# kt404c.net
KiCad netlist of a schematic drawn in Altium Designer
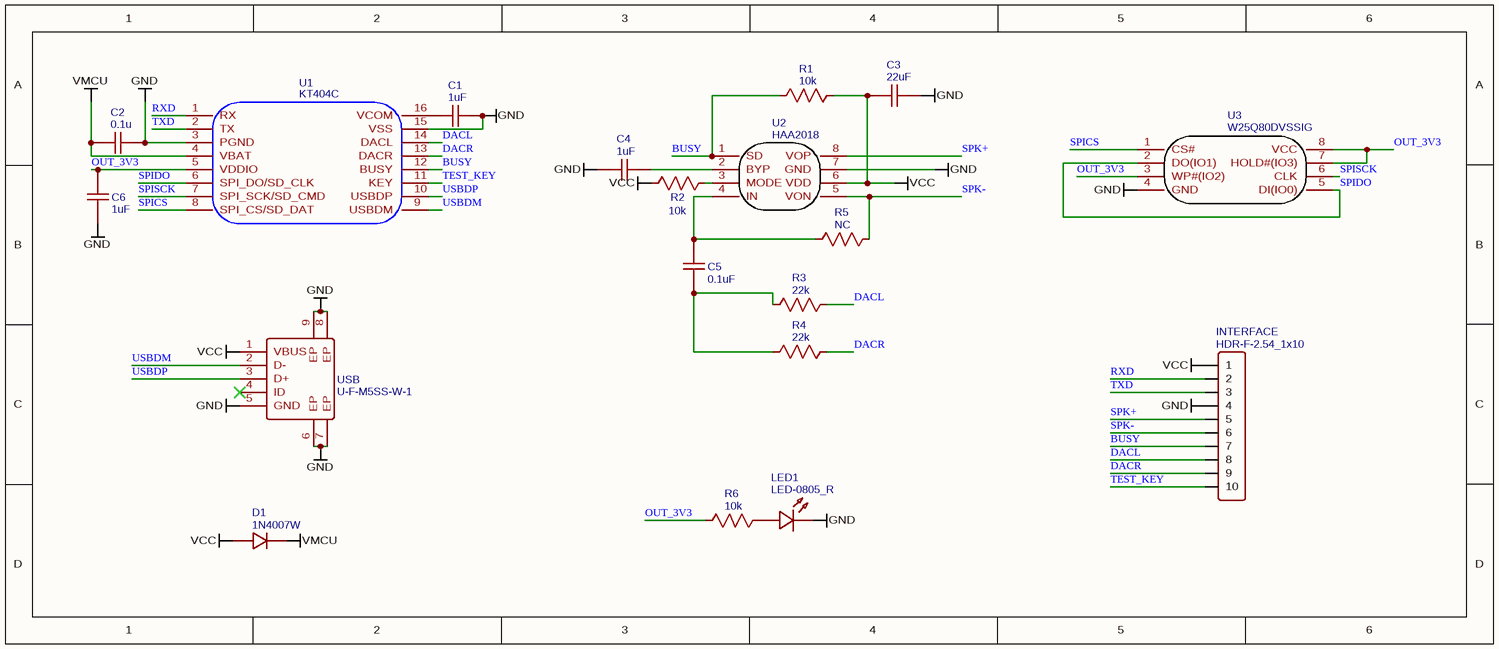
[diagram p0: kt404c.schdoc]

(export (version "E")
  (design (tool "Eeschema 10.0.6"))
  (components
    (comp (ref "C1")
      (value "1uF")
      (footprint "C0805")
      (fields (field (name "BOM_SUPPLIER PART") "C16834") (field (name "CONTRIBUTOR") "LCEDA_Lib"))
      (libsource (lib "altium-import") (part "root_0_1uF_"))
    )
    (comp (ref "C2")
      (value "0.1u")
      (footprint "C0805")
      (fields (field (name "BOM_SUPPLIER PART") "C1760") (field (name "CONTRIBUTOR") "LCEDA_Lib"))
      (libsource (lib "altium-import") (part "root_0_0.1u_"))
    )
    (comp (ref "C3")
      (value "22uF")
      (footprint "C0805")
      (fields (field (name "BOM_SUPPLIER PART") "C385040") (field (name "CONTRIBUTOR") "LCEDA_Lib"))
      (libsource (lib "altium-import") (part "root_0_22uF_"))
    )
    (comp (ref "C4")
      (value "1uF")
      (footprint "C0805")
      (fields (field (name "BOM_SUPPLIER PART") "C16834") (field (name "CONTRIBUTOR") "LCEDA_Lib"))
      (libsource (lib "altium-import") (part "root_0_1uF_"))
    )
    (comp (ref "C5")
      (value "0.1uF")
      (footprint "C0805")
      (fields (field (name "BOM_SUPPLIER PART") "C1760") (field (name "CONTRIBUTOR") "LCEDA_Lib"))
      (libsource (lib "altium-import") (part "root_3_0.1uF_"))
    )
    (comp (ref "C6")
      (value "1uF")
      (footprint "C0805")
      (fields (field (name "BOM_SUPPLIER PART") "C16834") (field (name "CONTRIBUTOR") "LCEDA_Lib"))
      (libsource (lib "altium-import") (part "root_3_1uF_"))
    )
    (comp (ref "D1")
      (value "1N4007W")
      (footprint "SOD-123_L2.8-W1.8-LS3.7-RD")
      (fields (field (name "BOM_SUPPLIER PART") "C328592") (field (name "CONTRIBUTOR") "LCEDA_Lib"))
      (libsource (lib "altium-import") (part "root_0_1N4007W_"))
    )
    (comp (ref "INTERFACE")
      (value "HDR-F-2.54_1x10")
      (footprint "HDR-F-2.54_1X10")
      (fields (field (name "BOM_SUPPLIER PART") "C57369") (field (name "CONTRIBUTOR") "LCEDA_Lib"))
      (libsource (lib "altium-import") (part "root_0_HDR-F-2.54_1x10_"))
    )
    (comp (ref "LED1")
      (value "LED-0805_R")
      (footprint "LED0805_RED")
      (fields
        (field (name "BOM_MANUFACTURER PART") "17-21SURC/S530-A3/TR8")
        (field (name "BOM_SUPPLIER PART") "C72037")
        (field (name "CONTRIBUTOR") "LCEDA_Lib")
      )
      (libsource (lib "altium-import") (part "root_0_LED-0805_R_"))
    )
    (comp (ref "R1")
      (value "10k")
      (footprint "R0805")
      (fields (field (name "BOM_SUPPLIER PART") "C2759650") (field (name "CONTRIBUTOR") "LCEDA_Lib"))
      (libsource (lib "altium-import") (part "root_0_10k_"))
    )
    (comp (ref "R2")
      (value "10k")
      (footprint "R0805")
      (fields (field (name "BOM_SUPPLIER PART") "C2759650") (field (name "CONTRIBUTOR") "LCEDA_Lib"))
      (libsource (lib "altium-import") (part "root_0_10k_"))
    )
    (comp (ref "R3")
      (value "22k")
      (footprint "R0805")
      (fields (field (name "BOM_SUPPLIER PART") "C114565") (field (name "CONTRIBUTOR") "LCEDA_Lib"))
      (libsource (lib "altium-import") (part "root_0_22k_"))
    )
    (comp (ref "R4")
      (value "22k")
      (footprint "R0805")
      (fields (field (name "BOM_SUPPLIER PART") "C114565") (field (name "CONTRIBUTOR") "LCEDA_Lib"))
      (libsource (lib "altium-import") (part "root_0_22k_"))
    )
    (comp (ref "R5")
      (value "NC")
      (footprint "R0805")
      (fields (field (name "CONTRIBUTOR") "LCEDA_Lib"))
      (libsource (lib "altium-import") (part "root_0_NC_"))
    )
    (comp (ref "R6")
      (value "10k")
      (footprint "R0805")
      (fields (field (name "BOM_SUPPLIER PART") "C2759650") (field (name "CONTRIBUTOR") "LCEDA_Lib"))
      (libsource (lib "altium-import") (part "root_0_10k_"))
    )
    (comp (ref "U1")
      (value "KT404C")
      (footprint "SOP16")
      (fields (field (name "CONTRIBUTOR") "BardYuan"))
      (libsource (lib "altium-import") (part "root_0_KT404C_"))
    )
    (comp (ref "U2")
      (value "HAA2018")
      (footprint "SOP8")
      (fields (field (name "CONTRIBUTOR") "xf1619"))
      (libsource (lib "altium-import") (part "root_0_HAA2018_"))
    )
    (comp (ref "U3")
      (value "W25Q80DVSSIG")
      (footprint "SOIC-8_L5.3-W5.3-P1.27-LS8.0-BL")
      (fields (field (name "BOM_SUPPLIER PART") "C14086"))
      (libsource (lib "altium-import") (part "root_0_W25Q80DVSSIG_"))
    )
    (comp (ref "USB")
      (value "U-F-M5SS-W-1")
      (footprint "MICRO-USB-SMD_MICRO-USB-A11")
      (fields (field (name "BOM_SUPPLIER PART") "C145783") (field (name "CONTRIBUTOR") "LCSC"))
      (libsource (lib "altium-import") (part "root_0_U-F-M5SS-W-1_"))
    )
  )
  (nets
    (net (code "1") (name "/BUSY") (class "Default")
      (node (ref "INTERFACE") (pin "7") (pinfunction "7_7") (pintype "passive"))
      (node (ref "R1") (pin "1") (pinfunction "1_1") (pintype "passive"))
      (node (ref "U1") (pin "12") (pinfunction "BUSY_12") (pintype "passive"))
      (node (ref "U2") (pin "1") (pinfunction "SD_1") (pintype "passive"))
    )
    (net (code "2") (name "/DACL") (class "Default")
      (node (ref "INTERFACE") (pin "8") (pinfunction "8_8") (pintype "passive"))
      (node (ref "R3") (pin "2") (pinfunction "2_2") (pintype "passive"))
      (node (ref "U1") (pin "14") (pinfunction "DACL_14") (pintype "passive"))
    )
    (net (code "3") (name "/DACR") (class "Default")
      (node (ref "INTERFACE") (pin "9") (pinfunction "9_9") (pintype "passive"))
      (node (ref "R4") (pin "2") (pinfunction "2_2") (pintype "passive"))
      (node (ref "U1") (pin "13") (pinfunction "DACR_13") (pintype "passive"))
    )
    (net (code "4") (name "/OUT_3V3") (class "Default")
      (node (ref "C6") (pin "1") (pinfunction "1_1") (pintype "passive"))
      (node (ref "R6") (pin "1") (pinfunction "1_1") (pintype "passive"))
      (node (ref "U1") (pin "5") (pinfunction "VDDIO_5") (pintype "passive"))
      (node (ref "U3") (pin "3") (pinfunction "WP#(IO2)_3") (pintype "passive"))
      (node (ref "U3") (pin "7") (pinfunction "HOLD#(IO3)_7") (pintype "passive"))
      (node (ref "U3") (pin "8") (pinfunction "VCC_8") (pintype "passive"))
    )
    (net (code "5") (name "/RXD") (class "Default")
      (node (ref "INTERFACE") (pin "2") (pinfunction "2_2") (pintype "passive"))
      (node (ref "U1") (pin "1") (pinfunction "RX_1") (pintype "passive"))
    )
    (net (code "6") (name "/SPICS") (class "Default")
      (node (ref "U1") (pin "8") (pinfunction "SPI_CS/SD_DAT_8") (pintype "passive"))
      (node (ref "U3") (pin "1") (pinfunction "CS#_1") (pintype "passive"))
    )
    (net (code "7") (name "/SPIDO") (class "Default")
      (node (ref "U1") (pin "6") (pinfunction "SPI_DO/SD_CLK_6") (pintype "passive"))
      (node (ref "U3") (pin "2") (pinfunction "DO(IO1)_2") (pintype "passive"))
      (node (ref "U3") (pin "5") (pinfunction "DI(IO0)_5") (pintype "passive"))
    )
    (net (code "8") (name "/SPISCK") (class "Default")
      (node (ref "U1") (pin "7") (pinfunction "SPI_SCK/SD_CMD_7") (pintype "passive"))
      (node (ref "U3") (pin "6") (pinfunction "CLK_6") (pintype "passive"))
    )
    (net (code "9") (name "/SPK+") (class "Default")
      (node (ref "INTERFACE") (pin "5") (pinfunction "5_5") (pintype "passive"))
      (node (ref "U2") (pin "8") (pinfunction "VOP_8") (pintype "passive"))
    )
    (net (code "10") (name "/SPK-") (class "Default")
      (node (ref "INTERFACE") (pin "6") (pinfunction "6_6") (pintype "passive"))
      (node (ref "R5") (pin "2") (pinfunction "2_2") (pintype "passive"))
      (node (ref "U2") (pin "5") (pinfunction "VON_5") (pintype "passive"))
    )
    (net (code "11") (name "/TEST_KEY") (class "Default")
      (node (ref "INTERFACE") (pin "10") (pinfunction "10_10") (pintype "passive"))
      (node (ref "U1") (pin "11") (pinfunction "KEY_11") (pintype "passive"))
    )
    (net (code "12") (name "/TXD") (class "Default")
      (node (ref "INTERFACE") (pin "3") (pinfunction "3_3") (pintype "passive"))
      (node (ref "U1") (pin "2") (pinfunction "TX_2") (pintype "passive"))
    )
    (net (code "13") (name "/USBDM") (class "Default")
      (node (ref "U1") (pin "9") (pinfunction "USBDM_9") (pintype "passive"))
      (node (ref "USB") (pin "2") (pinfunction "D-_2") (pintype "passive"))
    )
    (net (code "14") (name "/USBDP") (class "Default")
      (node (ref "U1") (pin "10") (pinfunction "USBDP_10") (pintype "passive"))
      (node (ref "USB") (pin "3") (pinfunction "D+_3") (pintype "passive"))
    )
    (net (code "15") (name "GND") (class "Default")
      (node (ref "C1") (pin "2") (pinfunction "2_2") (pintype "passive"))
      (node (ref "C2") (pin "2") (pinfunction "2_2") (pintype "passive"))
      (node (ref "C3") (pin "2") (pinfunction "2_2") (pintype "passive"))
      (node (ref "C4") (pin "1") (pinfunction "1_1") (pintype "passive"))
      (node (ref "C6") (pin "2") (pinfunction "2_2") (pintype "passive"))
      (node (ref "INTERFACE") (pin "4") (pinfunction "4_4") (pintype "passive"))
      (node (ref "LED1") (pin "2") (pinfunction "2_2") (pintype "passive"))
      (node (ref "U1") (pin "15") (pinfunction "VSS_15") (pintype "passive"))
      (node (ref "U1") (pin "3") (pinfunction "PGND_3") (pintype "passive"))
      (node (ref "U2") (pin "7") (pinfunction "GND_7") (pintype "passive"))
      (node (ref "U3") (pin "4") (pinfunction "GND_4") (pintype "passive"))
      (node (ref "USB") (pin "5") (pinfunction "GND_5") (pintype "passive"))
      (node (ref "USB") (pin "6") (pinfunction "EP_6") (pintype "passive"))
      (node (ref "USB") (pin "7") (pinfunction "EP_7") (pintype "passive"))
      (node (ref "USB") (pin "8") (pinfunction "EP_8") (pintype "passive"))
      (node (ref "USB") (pin "9") (pinfunction "EP_9") (pintype "passive"))
    )
    (net (code "16") (name "Net-(C5-Pad2)") (class "Default")
      (node (ref "C5") (pin "2") (pinfunction "2_2") (pintype "passive"))
      (node (ref "R3") (pin "1") (pinfunction "1_1") (pintype "passive"))
      (node (ref "R4") (pin "1") (pinfunction "1_1") (pintype "passive"))
    )
    (net (code "17") (name "Net-(LED1-Pad1)") (class "Default")
      (node (ref "LED1") (pin "1") (pinfunction "1_1") (pintype "passive"))
      (node (ref "R6") (pin "2") (pinfunction "2_2") (pintype "passive"))
    )
    (net (code "18") (name "Net-(U1-VCOM)") (class "Default")
      (node (ref "C1") (pin "1") (pinfunction "1_1") (pintype "passive"))
      (node (ref "U1") (pin "16") (pinfunction "VCOM_16") (pintype "passive"))
    )
    (net (code "19") (name "Net-(U2-BYP)") (class "Default")
      (node (ref "C4") (pin "2") (pinfunction "2_2") (pintype "passive"))
      (node (ref "U2") (pin "2") (pinfunction "BYP_2") (pintype "passive"))
    )
    (net (code "20") (name "Net-(U2-IN)") (class "Default")
      (node (ref "C5") (pin "1") (pinfunction "1_1") (pintype "passive"))
      (node (ref "R5") (pin "1") (pinfunction "1_1") (pintype "passive"))
      (node (ref "U2") (pin "4") (pinfunction "IN_4") (pintype "passive"))
    )
    (net (code "21") (name "Net-(U2-MODE)") (class "Default")
      (node (ref "R2") (pin "2") (pinfunction "2_2") (pintype "passive"))
      (node (ref "U2") (pin "3") (pinfunction "MODE_3") (pintype "passive"))
    )
    (net (code "22") (name "VCC") (class "Default")
      (node (ref "C3") (pin "1") (pinfunction "1_1") (pintype "passive"))
      (node (ref "D1") (pin "2") (pinfunction "2_2") (pintype "passive"))
      (node (ref "INTERFACE") (pin "1") (pinfunction "1_1") (pintype "passive"))
      (node (ref "R1") (pin "2") (pinfunction "2_2") (pintype "passive"))
      (node (ref "R2") (pin "1") (pinfunction "1_1") (pintype "passive"))
      (node (ref "U2") (pin "6") (pinfunction "VDD_6") (pintype "passive"))
      (node (ref "USB") (pin "1") (pinfunction "VBUS_1") (pintype "passive"))
    )
    (net (code "23") (name "VMCU") (class "Default")
      (node (ref "C2") (pin "1") (pinfunction "1_1") (pintype "passive"))
      (node (ref "D1") (pin "1") (pinfunction "1_1") (pintype "passive"))
      (node (ref "U1") (pin "4") (pinfunction "VBAT_4") (pintype "passive"))
    )
    (net (code "24") (name "unconnected-(USB-ID-Pad4)") (class "Default")
      (node (ref "USB") (pin "4") (pinfunction "ID_4") (pintype "passive+no_connect"))
    )
  )
)
